# HM_LightSensor.net
KiCad netlist of a schematic drawn in Altium Designer
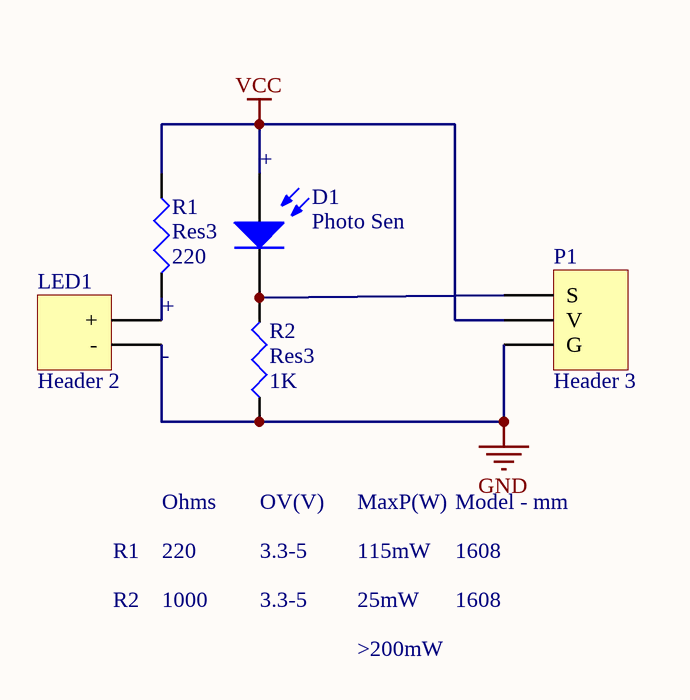
[diagram p0: HM_LightSensor.SchDoc]

(export (version "E")
  (design (tool "Eeschema 10.0.6"))
  (components
    (comp (ref "D1")
      (value "Photo Sen")
      (footprint "PIN2")
      (description "Photosensitive Diode")
      (fields (field (name "PUBLISHER") "Altium Limited"))
      (libsource (lib "Miscellaneous Devices") (part "Photo Sen"))
    )
    (comp (ref "LED1")
      (value "Header 2")
      (footprint "HDR1X2")
      (description "Header, 2-Pin")
      (fields (field (name "PUBLISHER") "Altium Limited"))
      (libsource (lib "Miscellaneous Connectors") (part "Header 2"))
    )
    (comp (ref "P1")
      (value "Header 3")
      (footprint "HDR1X3")
      (description "Header, 3-Pin")
      (fields (field (name "PUBLISHER") "Altium Limited"))
      (libsource (lib "Miscellaneous Connectors") (part "Header 3"))
    )
    (comp (ref "R1")
      (value "Res3")
      (footprint "J1-0603")
      (description "Resistor")
      (fields (field (name "ALTIUM_VALUE") "220") (field (name "PUBLISHER") "Altium Limited"))
      (libsource (lib "Miscellaneous Devices") (part "Res3"))
    )
    (comp (ref "R2")
      (value "Res3")
      (footprint "J1-0603")
      (description "Resistor")
      (fields (field (name "ALTIUM_VALUE") "1K") (field (name "PUBLISHER") "Altium Limited"))
      (libsource (lib "Miscellaneous Devices") (part "Res3"))
    )
  )
  (nets
    (net (code "1") (name "GND") (class "Default")
      (node (ref "LED1") (pin "1") (pinfunction "-_1") (pintype "passive"))
      (node (ref "P1") (pin "3") (pinfunction "G_3") (pintype "passive"))
      (node (ref "R2") (pin "1") (pinfunction "1_1") (pintype "passive"))
    )
    (net (code "2") (name "Net-(D1-K)") (class "Default")
      (node (ref "D1") (pin "2") (pinfunction "K_2") (pintype "passive"))
      (node (ref "P1") (pin "1") (pinfunction "S_1") (pintype "passive"))
      (node (ref "R2") (pin "2") (pinfunction "2_2") (pintype "passive"))
    )
    (net (code "3") (name "Net-(LED1-+)") (class "Default")
      (node (ref "LED1") (pin "2") (pinfunction "+_2") (pintype "passive"))
      (node (ref "R1") (pin "2") (pinfunction "2_2") (pintype "passive"))
    )
    (net (code "4") (name "VCC") (class "Default")
      (node (ref "D1") (pin "1") (pinfunction "A_1") (pintype "passive"))
      (node (ref "P1") (pin "2") (pinfunction "V_2") (pintype "passive"))
      (node (ref "R1") (pin "1") (pinfunction "1_1") (pintype "passive"))
    )
  )
)
